# uknc_sd_fdd.net
KiCad netlist of a schematic drawn in EAGLE
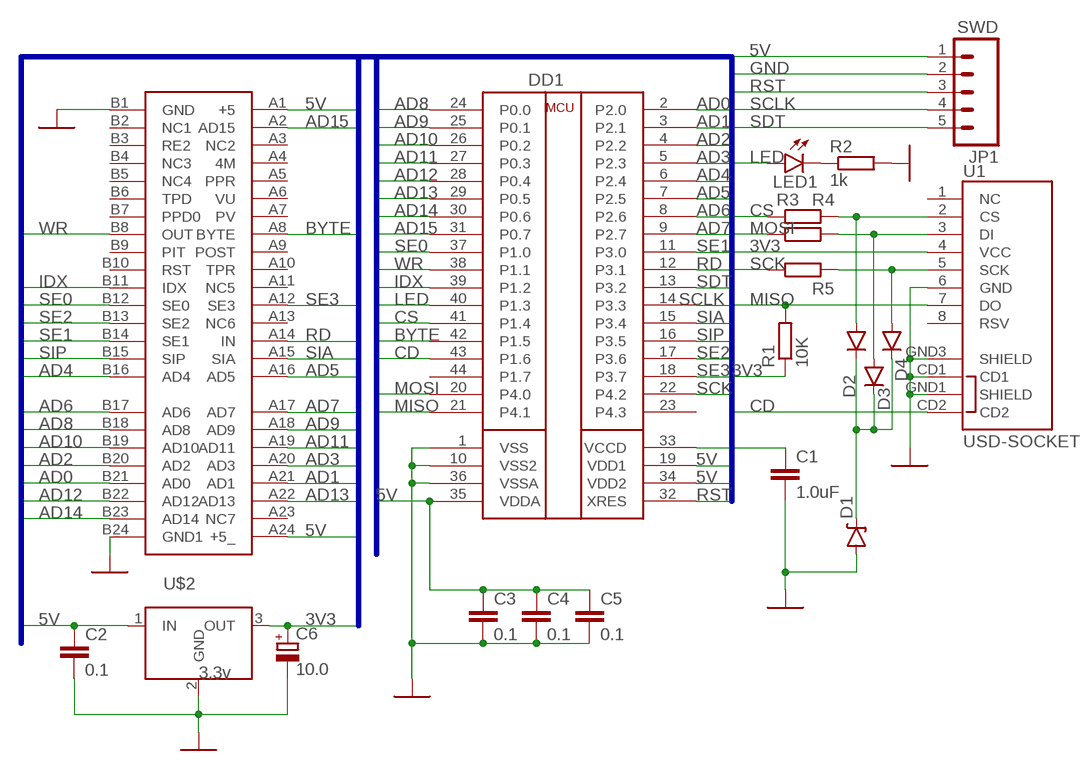
[diagram p0: schematic, sheet 1]

(export (version "E")
  (design (tool "Eeschema 10.0.6"))
  (components
    (comp (ref "C1")
      (value "1.0uF")
      (footprint "eagle-import:0805-CAP")
      (libsource (lib "eagle-import") (part "1.0UF-25V-+80/-20(0805){dblquote}"))
    )
    (comp (ref "C2")
      (value "0.1")
      (footprint "eagle-import:C0805")
      (libsource (lib "eagle-import") (part "C-EUC0805"))
    )
    (comp (ref "C3")
      (value "0.1")
      (footprint "eagle-import:C0805")
      (libsource (lib "eagle-import") (part "C-EUC0805"))
    )
    (comp (ref "C4")
      (value "0.1")
      (footprint "eagle-import:C0805")
      (libsource (lib "eagle-import") (part "C-EUC0805"))
    )
    (comp (ref "C5")
      (value "0.1")
      (footprint "eagle-import:C0805")
      (libsource (lib "eagle-import") (part "C-EUC0805"))
    )
    (comp (ref "C6")
      (value "10.0")
      (footprint "eagle-import:E1,8-4")
      (libsource (lib "eagle-import") (part "CPOL-EUE1.8-4"))
    )
    (comp (ref "D1")
      (value "DIODE-ZENERPTH")
      (footprint "eagle-import:DIODE-ZENER")
      (libsource (lib "eagle-import") (part "DIODE-ZENERPTH"))
    )
    (comp (ref "D2")
      (value "DIODEPTH")
      (footprint "eagle-import:DIODE-1N4001")
      (libsource (lib "eagle-import") (part "DIODEPTH"))
    )
    (comp (ref "D3")
      (value "DIODEPTH")
      (footprint "eagle-import:DIODE-1N4001")
      (libsource (lib "eagle-import") (part "DIODEPTH"))
    )
    (comp (ref "D4")
      (value "DIODEPTH")
      (footprint "eagle-import:DIODE-1N4001")
      (libsource (lib "eagle-import") (part "DIODEPTH"))
    )
    (comp (ref "DD1")
      (value "CY8C4245AXI")
      (footprint "eagle-import:TQFP-44")
      (libsource (lib "eagle-import") (part "CY8C4245AXI"))
    )
    (comp (ref "JP1")
      (value "SWD")
      (footprint "eagle-import:1X05")
      (libsource (lib "eagle-import") (part "M05PTH"))
    )
    (comp (ref "LED1")
      (value "LED1206")
      (footprint "eagle-import:LED-1206")
      (libsource (lib "eagle-import") (part "LED1206"))
    )
    (comp (ref "R1")
      (value "10K")
      (footprint "eagle-import:M0805")
      (libsource (lib "eagle-import") (part "R-EU_M0805"))
    )
    (comp (ref "R2")
      (value "1k")
      (footprint "eagle-import:R0805")
      (libsource (lib "eagle-import") (part "R-EU_R0805"))
    )
    (comp (ref "R3")
      (value "R-EU_R0805")
      (footprint "eagle-import:R0805")
      (libsource (lib "eagle-import") (part "R-EU_R0805"))
    )
    (comp (ref "R4")
      (value "R-EU_R0805")
      (footprint "eagle-import:R0805")
      (libsource (lib "eagle-import") (part "R-EU_R0805"))
    )
    (comp (ref "R5")
      (value "R-EU_R0805")
      (footprint "eagle-import:R0805")
      (libsource (lib "eagle-import") (part "R-EU_R0805"))
    )
    (comp (ref "U$1")
      (value "SNP")
      (footprint "eagle-import:SNP15-48-BOARD")
      (libsource (lib "eagle-import") (part "SNP"))
    )
    (comp (ref "U$2")
      (value "3.3v")
      (footprint "eagle-import:1235B")
      (libsource (lib "eagle-import") (part "1235B"))
    )
    (comp (ref "U1")
      (value "USD-SOCKET")
      (footprint "eagle-import:MICROSD_1_1")
      (libsource (lib "eagle-import") (part "USD-SOCKET"))
    )
  )
  (nets
    (net (code "1") (name "/3V3") (class "Default")
      (node (ref "C6") (pin "+") (pinfunction "+_+") (pintype "passive"))
      (node (ref "R1") (pin "1") (pinfunction "1_1") (pintype "passive"))
      (node (ref "U$2") (pin "3") (pinfunction "OUT_3") (pintype "bidirectional"))
      (node (ref "U1") (pin "4") (pinfunction "VCC_4") (pintype "bidirectional"))
    )
    (net (code "2") (name "/5V") (class "Default")
      (node (ref "C2") (pin "1") (pinfunction "1_1") (pintype "passive"))
      (node (ref "C3") (pin "1") (pinfunction "1_1") (pintype "passive"))
      (node (ref "C4") (pin "1") (pinfunction "1_1") (pintype "passive"))
      (node (ref "C5") (pin "1") (pinfunction "1_1") (pintype "passive"))
      (node (ref "DD1") (pin "19") (pinfunction "VDD1_19") (pintype "bidirectional"))
      (node (ref "DD1") (pin "34") (pinfunction "VDD2_34") (pintype "bidirectional"))
      (node (ref "DD1") (pin "35") (pinfunction "VDDA_35") (pintype "bidirectional"))
      (node (ref "JP1") (pin "1") (pinfunction "1_1") (pintype "passive"))
      (node (ref "U$1") (pin "A1") (pinfunction "+5_A1") (pintype "bidirectional"))
      (node (ref "U$1") (pin "A24") (pinfunction "+5__A24") (pintype "bidirectional"))
      (node (ref "U$2") (pin "1") (pinfunction "IN_1") (pintype "bidirectional"))
    )
    (net (code "3") (name "/AD0") (class "Default")
      (node (ref "DD1") (pin "2") (pinfunction "P2.0_2") (pintype "bidirectional"))
      (node (ref "U$1") (pin "B21") (pinfunction "AD0_B21") (pintype "bidirectional"))
    )
    (net (code "4") (name "/AD1") (class "Default")
      (node (ref "DD1") (pin "3") (pinfunction "P2.1_3") (pintype "bidirectional"))
      (node (ref "U$1") (pin "A21") (pinfunction "AD1_A21") (pintype "bidirectional"))
    )
    (net (code "5") (name "/AD2") (class "Default")
      (node (ref "DD1") (pin "4") (pinfunction "P2.2_4") (pintype "bidirectional"))
      (node (ref "U$1") (pin "B20") (pinfunction "AD2_B20") (pintype "bidirectional"))
    )
    (net (code "6") (name "/AD3") (class "Default")
      (node (ref "DD1") (pin "5") (pinfunction "P2.3_5") (pintype "bidirectional"))
      (node (ref "U$1") (pin "A20") (pinfunction "AD3_A20") (pintype "bidirectional"))
    )
    (net (code "7") (name "/AD4") (class "Default")
      (node (ref "DD1") (pin "6") (pinfunction "P2.4_6") (pintype "bidirectional"))
      (node (ref "U$1") (pin "B16") (pinfunction "AD4_B16") (pintype "bidirectional"))
    )
    (net (code "8") (name "/AD5") (class "Default")
      (node (ref "DD1") (pin "7") (pinfunction "P2.5_7") (pintype "bidirectional"))
      (node (ref "U$1") (pin "A16") (pinfunction "AD5_A16") (pintype "bidirectional"))
    )
    (net (code "9") (name "/AD6") (class "Default")
      (node (ref "DD1") (pin "8") (pinfunction "P2.6_8") (pintype "bidirectional"))
      (node (ref "U$1") (pin "B17") (pinfunction "AD6_B17") (pintype "bidirectional"))
    )
    (net (code "10") (name "/AD7") (class "Default")
      (node (ref "DD1") (pin "9") (pinfunction "P2.7_9") (pintype "bidirectional"))
      (node (ref "U$1") (pin "A17") (pinfunction "AD7_A17") (pintype "bidirectional"))
    )
    (net (code "11") (name "/AD8") (class "Default")
      (node (ref "DD1") (pin "24") (pinfunction "P0.0_24") (pintype "bidirectional"))
      (node (ref "U$1") (pin "B18") (pinfunction "AD8_B18") (pintype "bidirectional"))
    )
    (net (code "12") (name "/AD9") (class "Default")
      (node (ref "DD1") (pin "25") (pinfunction "P0.1_25") (pintype "bidirectional"))
      (node (ref "U$1") (pin "A18") (pinfunction "AD9_A18") (pintype "bidirectional"))
    )
    (net (code "13") (name "/AD10") (class "Default")
      (node (ref "DD1") (pin "26") (pinfunction "P0.2_26") (pintype "bidirectional"))
      (node (ref "U$1") (pin "B19") (pinfunction "AD10_B19") (pintype "bidirectional"))
    )
    (net (code "14") (name "/AD11") (class "Default")
      (node (ref "DD1") (pin "27") (pinfunction "P0.3_27") (pintype "bidirectional"))
      (node (ref "U$1") (pin "A19") (pinfunction "AD11_A19") (pintype "bidirectional"))
    )
    (net (code "15") (name "/AD12") (class "Default")
      (node (ref "DD1") (pin "28") (pinfunction "P0.4_28") (pintype "bidirectional"))
      (node (ref "U$1") (pin "B22") (pinfunction "AD12_B22") (pintype "bidirectional"))
    )
    (net (code "16") (name "/AD13") (class "Default")
      (node (ref "DD1") (pin "29") (pinfunction "P0.5_29") (pintype "bidirectional"))
      (node (ref "U$1") (pin "A22") (pinfunction "AD13_A22") (pintype "bidirectional"))
    )
    (net (code "17") (name "/AD14") (class "Default")
      (node (ref "DD1") (pin "30") (pinfunction "P0.6_30") (pintype "bidirectional"))
      (node (ref "U$1") (pin "B23") (pinfunction "AD14_B23") (pintype "bidirectional"))
    )
    (net (code "18") (name "/AD15") (class "Default")
      (node (ref "DD1") (pin "31") (pinfunction "P0.7_31") (pintype "bidirectional"))
      (node (ref "U$1") (pin "A2") (pinfunction "AD15_A2") (pintype "bidirectional"))
    )
    (net (code "19") (name "/BYTE") (class "Default")
      (node (ref "DD1") (pin "42") (pinfunction "P1.5_42") (pintype "bidirectional"))
      (node (ref "U$1") (pin "A8") (pinfunction "BYTE_A8") (pintype "bidirectional"))
    )
    (net (code "20") (name "/CD") (class "Default")
      (node (ref "DD1") (pin "43") (pinfunction "P1.6_43") (pintype "bidirectional"))
      (node (ref "U1") (pin "CD2") (pinfunction "CD2_CD2") (pintype "bidirectional"))
    )
    (net (code "21") (name "/CS") (class "Default")
      (node (ref "DD1") (pin "41") (pinfunction "P1.4_41") (pintype "bidirectional"))
      (node (ref "R3") (pin "1") (pinfunction "1_1") (pintype "passive"))
    )
    (net (code "22") (name "/IDX") (class "Default")
      (node (ref "DD1") (pin "39") (pinfunction "P1.2_39") (pintype "bidirectional"))
      (node (ref "U$1") (pin "B11") (pinfunction "IDX_B11") (pintype "bidirectional"))
    )
    (net (code "23") (name "/LED") (class "Default")
      (node (ref "DD1") (pin "40") (pinfunction "P1.3_40") (pintype "bidirectional"))
      (node (ref "LED1") (pin "A") (pinfunction "A_A") (pintype "passive"))
    )
    (net (code "24") (name "/MISO") (class "Default")
      (node (ref "DD1") (pin "21") (pinfunction "P4.1_21") (pintype "bidirectional"))
      (node (ref "R1") (pin "2") (pinfunction "2_2") (pintype "passive"))
      (node (ref "U1") (pin "7") (pinfunction "DO_7") (pintype "bidirectional"))
    )
    (net (code "25") (name "/MOSI") (class "Default")
      (node (ref "DD1") (pin "20") (pinfunction "P4.0_20") (pintype "bidirectional"))
      (node (ref "R4") (pin "1") (pinfunction "1_1") (pintype "passive"))
    )
    (net (code "26") (name "/RD") (class "Default")
      (node (ref "DD1") (pin "12") (pinfunction "P3.1_12") (pintype "bidirectional"))
      (node (ref "U$1") (pin "A14") (pinfunction "IN_A14") (pintype "bidirectional"))
    )
    (net (code "27") (name "/RST") (class "Default")
      (node (ref "DD1") (pin "32") (pinfunction "XRES_32") (pintype "bidirectional"))
      (node (ref "JP1") (pin "3") (pinfunction "3_3") (pintype "passive"))
    )
    (net (code "28") (name "/SCK") (class "Default")
      (node (ref "DD1") (pin "22") (pinfunction "P4.2_22") (pintype "bidirectional"))
      (node (ref "R5") (pin "1") (pinfunction "1_1") (pintype "passive"))
    )
    (net (code "29") (name "/SCLK") (class "Default")
      (node (ref "DD1") (pin "14") (pinfunction "P3.3_14") (pintype "bidirectional"))
      (node (ref "JP1") (pin "4") (pinfunction "4_4") (pintype "passive"))
    )
    (net (code "30") (name "/SDT") (class "Default")
      (node (ref "DD1") (pin "13") (pinfunction "P3.2_13") (pintype "bidirectional"))
      (node (ref "JP1") (pin "5") (pinfunction "5_5") (pintype "passive"))
    )
    (net (code "31") (name "/SE0") (class "Default")
      (node (ref "DD1") (pin "37") (pinfunction "P1.0_37") (pintype "bidirectional"))
      (node (ref "U$1") (pin "B12") (pinfunction "SE0_B12") (pintype "bidirectional"))
    )
    (net (code "32") (name "/SE1") (class "Default")
      (node (ref "DD1") (pin "11") (pinfunction "P3.0_11") (pintype "bidirectional"))
      (node (ref "U$1") (pin "B14") (pinfunction "SE1_B14") (pintype "bidirectional"))
    )
    (net (code "33") (name "/SE2") (class "Default")
      (node (ref "DD1") (pin "17") (pinfunction "P3.6_17") (pintype "bidirectional"))
      (node (ref "U$1") (pin "B13") (pinfunction "SE2_B13") (pintype "bidirectional"))
    )
    (net (code "34") (name "/SE3") (class "Default")
      (node (ref "DD1") (pin "18") (pinfunction "P3.7_18") (pintype "bidirectional"))
      (node (ref "U$1") (pin "A12") (pinfunction "SE3_A12") (pintype "bidirectional"))
    )
    (net (code "35") (name "/SIA") (class "Default")
      (node (ref "DD1") (pin "15") (pinfunction "P3.4_15") (pintype "bidirectional"))
      (node (ref "U$1") (pin "A15") (pinfunction "SIA_A15") (pintype "bidirectional"))
    )
    (net (code "36") (name "/SIP") (class "Default")
      (node (ref "DD1") (pin "16") (pinfunction "P3.5_16") (pintype "bidirectional"))
      (node (ref "U$1") (pin "B15") (pinfunction "SIP_B15") (pintype "bidirectional"))
    )
    (net (code "37") (name "/WR") (class "Default")
      (node (ref "DD1") (pin "38") (pinfunction "P1.1_38") (pintype "bidirectional"))
      (node (ref "U$1") (pin "B8") (pinfunction "OUT_B8") (pintype "bidirectional"))
    )
    (net (code "38") (name "GND") (class "Default")
      (node (ref "C1") (pin "2") (pinfunction "2_2") (pintype "passive"))
      (node (ref "C2") (pin "2") (pinfunction "2_2") (pintype "passive"))
      (node (ref "C3") (pin "2") (pinfunction "2_2") (pintype "passive"))
      (node (ref "C4") (pin "2") (pinfunction "2_2") (pintype "passive"))
      (node (ref "C5") (pin "2") (pinfunction "2_2") (pintype "passive"))
      (node (ref "C6") (pin "-") (pinfunction "-_-") (pintype "passive"))
      (node (ref "D1") (pin "P$2") (pinfunction "A_P$2") (pintype "passive"))
      (node (ref "DD1") (pin "1") (pinfunction "VSS_1") (pintype "bidirectional"))
      (node (ref "DD1") (pin "10") (pinfunction "VSS2_10") (pintype "bidirectional"))
      (node (ref "DD1") (pin "36") (pinfunction "VSSA_36") (pintype "bidirectional"))
      (node (ref "JP1") (pin "2") (pinfunction "2_2") (pintype "passive"))
      (node (ref "R2") (pin "2") (pinfunction "2_2") (pintype "passive"))
      (node (ref "U$1") (pin "B1") (pinfunction "GND_B1") (pintype "bidirectional"))
      (node (ref "U$1") (pin "B24") (pinfunction "GND1_B24") (pintype "bidirectional"))
      (node (ref "U$2") (pin "2") (pinfunction "GND_2") (pintype "bidirectional"))
      (node (ref "U1") (pin "6") (pinfunction "GND_6") (pintype "bidirectional"))
      (node (ref "U1") (pin "CD1") (pinfunction "CD1_CD1") (pintype "bidirectional"))
      (node (ref "U1") (pin "GND1") (pinfunction "SHIELD_GND1") (pintype "bidirectional"))
      (node (ref "U1") (pin "GND3") (pinfunction "SHIELD_GND3") (pintype "bidirectional"))
    )
    (net (code "39") (name "Net-(D1-C)") (class "Default")
      (node (ref "D1") (pin "P$1") (pinfunction "C_P$1") (pintype "passive"))
      (node (ref "D2") (pin "C") (pinfunction "C_C") (pintype "passive"))
      (node (ref "D3") (pin "C") (pinfunction "C_C") (pintype "passive"))
      (node (ref "D4") (pin "C") (pinfunction "C_C") (pintype "passive"))
    )
    (net (code "40") (name "Net-(DD1-VCCD)") (class "Default")
      (node (ref "C1") (pin "1") (pinfunction "1_1") (pintype "passive"))
      (node (ref "DD1") (pin "33") (pinfunction "VCCD_33") (pintype "bidirectional"))
    )
    (net (code "41") (name "Net-(LED1-PadC)") (class "Default")
      (node (ref "LED1") (pin "C") (pinfunction "C_C") (pintype "passive"))
      (node (ref "R2") (pin "1") (pinfunction "1_1") (pintype "passive"))
    )
    (net (code "42") (name "Net-(U1-CS)") (class "Default")
      (node (ref "D2") (pin "A") (pinfunction "A_A") (pintype "passive"))
      (node (ref "R3") (pin "2") (pinfunction "2_2") (pintype "passive"))
      (node (ref "U1") (pin "2") (pinfunction "CS_2") (pintype "bidirectional"))
    )
    (net (code "43") (name "Net-(U1-DI)") (class "Default")
      (node (ref "D3") (pin "A") (pinfunction "A_A") (pintype "passive"))
      (node (ref "R4") (pin "2") (pinfunction "2_2") (pintype "passive"))
      (node (ref "U1") (pin "3") (pinfunction "DI_3") (pintype "bidirectional"))
    )
    (net (code "44") (name "Net-(U1-SCK)") (class "Default")
      (node (ref "D4") (pin "A") (pinfunction "A_A") (pintype "passive"))
      (node (ref "R5") (pin "2") (pinfunction "2_2") (pintype "passive"))
      (node (ref "U1") (pin "5") (pinfunction "SCK_5") (pintype "bidirectional"))
    )
    (net (code "45") (name "unconnected-(DD1-P1.7-Pad44)") (class "Default")
      (node (ref "DD1") (pin "44") (pinfunction "P1.7_44") (pintype "bidirectional"))
    )
    (net (code "46") (name "unconnected-(DD1-P4.3-Pad23)") (class "Default")
      (node (ref "DD1") (pin "23") (pinfunction "P4.3_23") (pintype "bidirectional"))
    )
    (net (code "47") (name "unconnected-(U$1-4M-PadA4)") (class "Default")
      (node (ref "U$1") (pin "A4") (pinfunction "4M_A4") (pintype "bidirectional"))
    )
    (net (code "48") (name "unconnected-(U$1-NC1-PadB2)") (class "Default")
      (node (ref "U$1") (pin "B2") (pinfunction "NC1_B2") (pintype "bidirectional"))
    )
    (net (code "49") (name "unconnected-(U$1-NC2-PadA3)") (class "Default")
      (node (ref "U$1") (pin "A3") (pinfunction "NC2_A3") (pintype "bidirectional"))
    )
    (net (code "50") (name "unconnected-(U$1-NC3-PadB4)") (class "Default")
      (node (ref "U$1") (pin "B4") (pinfunction "NC3_B4") (pintype "bidirectional"))
    )
    (net (code "51") (name "unconnected-(U$1-NC4-PadB5)") (class "Default")
      (node (ref "U$1") (pin "B5") (pinfunction "NC4_B5") (pintype "bidirectional"))
    )
    (net (code "52") (name "unconnected-(U$1-NC5-PadA11)") (class "Default")
      (node (ref "U$1") (pin "A11") (pinfunction "NC5_A11") (pintype "bidirectional"))
    )
    (net (code "53") (name "unconnected-(U$1-NC6-PadA13)") (class "Default")
      (node (ref "U$1") (pin "A13") (pinfunction "NC6_A13") (pintype "bidirectional"))
    )
    (net (code "54") (name "unconnected-(U$1-NC7-PadA23)") (class "Default")
      (node (ref "U$1") (pin "A23") (pinfunction "NC7_A23") (pintype "bidirectional"))
    )
    (net (code "55") (name "unconnected-(U$1-PIT-PadB9)") (class "Default")
      (node (ref "U$1") (pin "B9") (pinfunction "PIT_B9") (pintype "bidirectional"))
    )
    (net (code "56") (name "unconnected-(U$1-POST-PadA9)") (class "Default")
      (node (ref "U$1") (pin "A9") (pinfunction "POST_A9") (pintype "bidirectional"))
    )
    (net (code "57") (name "unconnected-(U$1-PPD0-PadB7)") (class "Default")
      (node (ref "U$1") (pin "B7") (pinfunction "PPD0_B7") (pintype "bidirectional"))
    )
    (net (code "58") (name "unconnected-(U$1-PPR-PadA5)") (class "Default")
      (node (ref "U$1") (pin "A5") (pinfunction "PPR_A5") (pintype "bidirectional"))
    )
    (net (code "59") (name "unconnected-(U$1-PV-PadA7)") (class "Default")
      (node (ref "U$1") (pin "A7") (pinfunction "PV_A7") (pintype "bidirectional"))
    )
    (net (code "60") (name "unconnected-(U$1-RE2-PadB3)") (class "Default")
      (node (ref "U$1") (pin "B3") (pinfunction "RE2_B3") (pintype "bidirectional"))
    )
    (net (code "61") (name "unconnected-(U$1-RST-PadB10)") (class "Default")
      (node (ref "U$1") (pin "B10") (pinfunction "RST_B10") (pintype "bidirectional"))
    )
    (net (code "62") (name "unconnected-(U$1-TPD-PadB6)") (class "Default")
      (node (ref "U$1") (pin "B6") (pinfunction "TPD_B6") (pintype "bidirectional"))
    )
    (net (code "63") (name "unconnected-(U$1-TPR-PadA10)") (class "Default")
      (node (ref "U$1") (pin "A10") (pinfunction "TPR_A10") (pintype "bidirectional"))
    )
    (net (code "64") (name "unconnected-(U$1-VU-PadA6)") (class "Default")
      (node (ref "U$1") (pin "A6") (pinfunction "VU_A6") (pintype "bidirectional"))
    )
    (net (code "65") (name "unconnected-(U1-NC-Pad1)") (class "Default")
      (node (ref "U1") (pin "1") (pinfunction "NC_1") (pintype "bidirectional"))
    )
    (net (code "66") (name "unconnected-(U1-RSV-Pad8)") (class "Default")
      (node (ref "U1") (pin "8") (pinfunction "RSV_8") (pintype "bidirectional"))
    )
  )
)
